# oilmon_intf_vr_photon.net
KiCad netlist of a schematic drawn in EAGLE
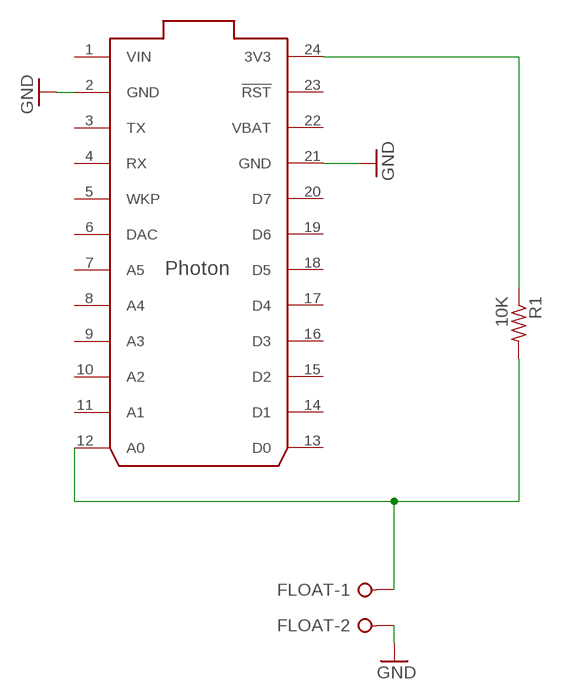
[diagram p0: schematic, sheet 1]

(export (version "E")
  (design (tool "Eeschema 10.0.6"))
  (components
    (comp (ref "FLOAT")
      (value "W237-02P")
      (footprint "eagle-import:W237-132")
      (libsource (lib "eagle-import") (part "W237-02P"))
    )
    (comp (ref "PHOTON")
      (value "PHOTON_WITH_HEADERS")
      (footprint "eagle-import:PHOTON")
      (libsource (lib "eagle-import") (part "PHOTON_WITH_HEADERS"))
    )
    (comp (ref "R1")
      (value "10K")
      (footprint "eagle-import:0207_10")
      (libsource (lib "eagle-import") (part "R-US_0207/10"))
    )
  )
  (nets
    (net (code "1") (name "/VBAT") (class "Default")
      (node (ref "PHOTON") (pin "22") (pinfunction "VBAT_22") (pintype "power_in"))
    )
    (net (code "2") (name "/VIN") (class "Default")
      (node (ref "PHOTON") (pin "1") (pinfunction "VIN_1") (pintype "power_in"))
    )
    (net (code "3") (name "GND") (class "Default")
      (node (ref "FLOAT") (pin "2") (pinfunction "KL_2") (pintype "passive"))
      (node (ref "PHOTON") (pin "2") (pinfunction "GND_2") (pintype "power_in"))
      (node (ref "PHOTON") (pin "21") (pinfunction "GND_21") (pintype "power_in"))
    )
    (net (code "4") (name "Net-(FLOATA-KL)") (class "Default")
      (node (ref "FLOAT") (pin "1") (pinfunction "KL_1") (pintype "passive"))
      (node (ref "PHOTON") (pin "12") (pinfunction "A0_12") (pintype "bidirectional"))
      (node (ref "R1") (pin "2") (pinfunction "2_2") (pintype "passive"))
    )
    (net (code "5") (name "Net-(PHOTON-3V3)") (class "Default")
      (node (ref "PHOTON") (pin "24") (pinfunction "3V3_24") (pintype "power_in"))
      (node (ref "R1") (pin "1") (pinfunction "1_1") (pintype "passive"))
    )
    (net (code "6") (name "unconnected-(PHOTON-A1-Pad11)") (class "Default")
      (node (ref "PHOTON") (pin "11") (pinfunction "A1_11") (pintype "bidirectional"))
    )
    (net (code "7") (name "unconnected-(PHOTON-A2-Pad10)") (class "Default")
      (node (ref "PHOTON") (pin "10") (pinfunction "A2_10") (pintype "bidirectional"))
    )
    (net (code "8") (name "unconnected-(PHOTON-A3-Pad9)") (class "Default")
      (node (ref "PHOTON") (pin "9") (pinfunction "A3_9") (pintype "bidirectional"))
    )
    (net (code "9") (name "unconnected-(PHOTON-A4-Pad8)") (class "Default")
      (node (ref "PHOTON") (pin "8") (pinfunction "A4_8") (pintype "bidirectional"))
    )
    (net (code "10") (name "unconnected-(PHOTON-A5-Pad7)") (class "Default")
      (node (ref "PHOTON") (pin "7") (pinfunction "A5_7") (pintype "bidirectional"))
    )
    (net (code "11") (name "unconnected-(PHOTON-D0-Pad13)") (class "Default")
      (node (ref "PHOTON") (pin "13") (pinfunction "D0_13") (pintype "bidirectional"))
    )
    (net (code "12") (name "unconnected-(PHOTON-D1-Pad14)") (class "Default")
      (node (ref "PHOTON") (pin "14") (pinfunction "D1_14") (pintype "bidirectional"))
    )
    (net (code "13") (name "unconnected-(PHOTON-D2-Pad15)") (class "Default")
      (node (ref "PHOTON") (pin "15") (pinfunction "D2_15") (pintype "bidirectional"))
    )
    (net (code "14") (name "unconnected-(PHOTON-D3-Pad16)") (class "Default")
      (node (ref "PHOTON") (pin "16") (pinfunction "D3_16") (pintype "bidirectional"))
    )
    (net (code "15") (name "unconnected-(PHOTON-D4-Pad17)") (class "Default")
      (node (ref "PHOTON") (pin "17") (pinfunction "D4_17") (pintype "bidirectional"))
    )
    (net (code "16") (name "unconnected-(PHOTON-D5-Pad18)") (class "Default")
      (node (ref "PHOTON") (pin "18") (pinfunction "D5_18") (pintype "bidirectional"))
    )
    (net (code "17") (name "unconnected-(PHOTON-D6-Pad19)") (class "Default")
      (node (ref "PHOTON") (pin "19") (pinfunction "D6_19") (pintype "bidirectional"))
    )
    (net (code "18") (name "unconnected-(PHOTON-D7-Pad20)") (class "Default")
      (node (ref "PHOTON") (pin "20") (pinfunction "D7_20") (pintype "bidirectional"))
    )
    (net (code "19") (name "unconnected-(PHOTON-DAC-Pad6)") (class "Default")
      (node (ref "PHOTON") (pin "6") (pinfunction "DAC_6") (pintype "bidirectional"))
    )
    (net (code "20") (name "unconnected-(PHOTON-RX-Pad4)") (class "Default")
      (node (ref "PHOTON") (pin "4") (pinfunction "RX_4") (pintype "bidirectional"))
    )
    (net (code "21") (name "unconnected-(PHOTON-TX-Pad3)") (class "Default")
      (node (ref "PHOTON") (pin "3") (pinfunction "TX_3") (pintype "bidirectional"))
    )
    (net (code "22") (name "unconnected-(PHOTON-WKP-Pad5)") (class "Default")
      (node (ref "PHOTON") (pin "5") (pinfunction "WKP_5") (pintype "bidirectional"))
    )
    (net (code "23") (name "unconnected-(PHOTON-~{RST}-Pad23)") (class "Default")
      (node (ref "PHOTON") (pin "23") (pinfunction "~{RST}_23") (pintype "bidirectional"))
    )
  )
)
